# phase1_sheet_97101994.net
KiCad netlist of a schematic drawn in Altium Designer
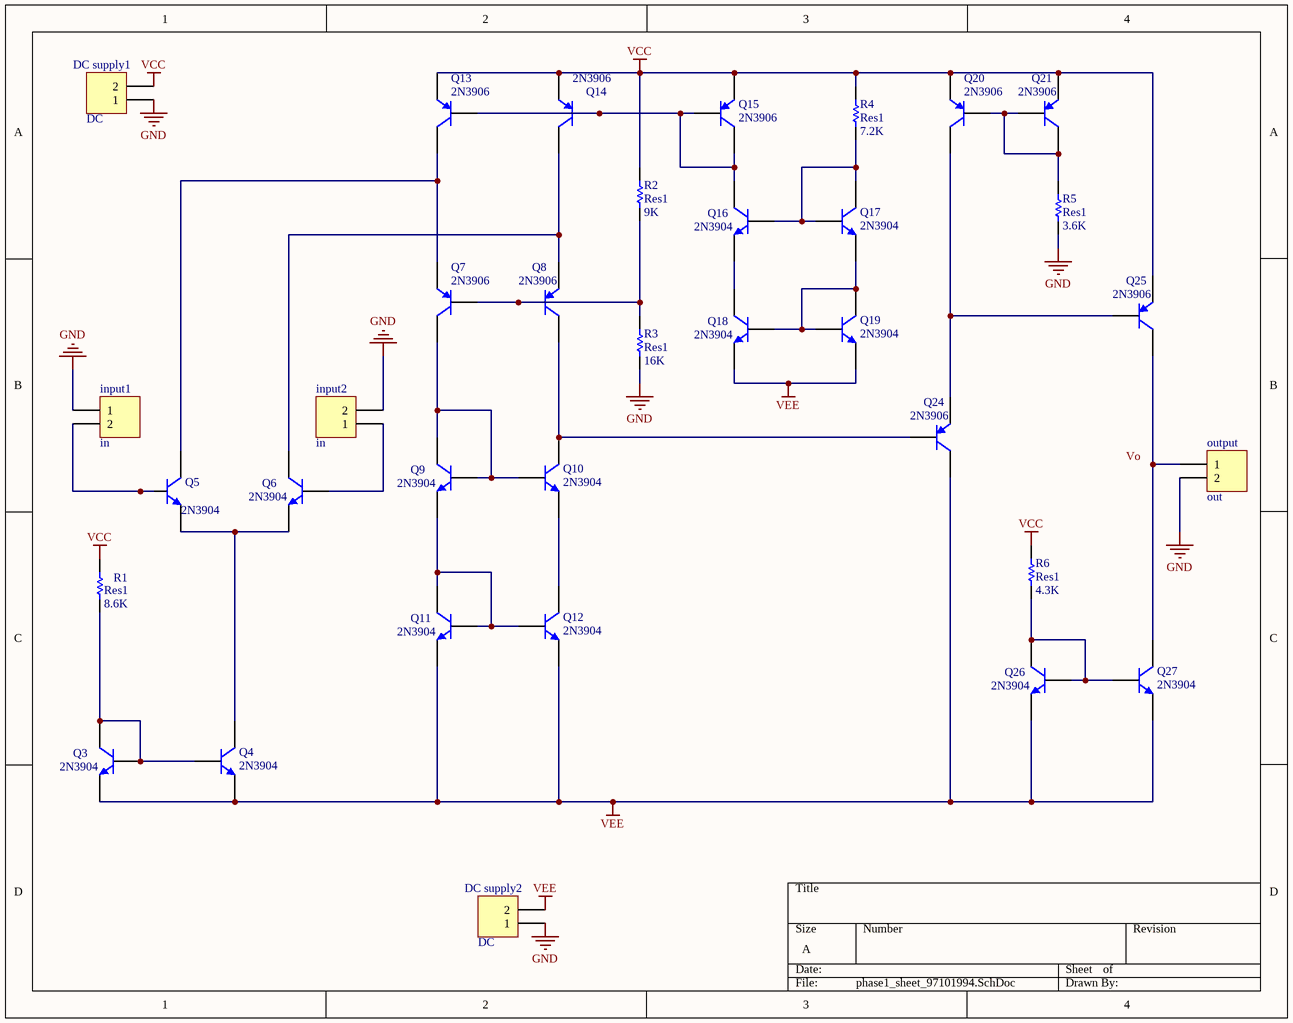
[diagram p0: phase1_sheet_97101994.SchDoc]

(export (version "E")
  (design (tool "Eeschema 10.0.6"))
  (components
    (comp (ref "DC supply1")
      (value "DC")
      (footprint "HDR1X2")
      (description "Header, 2-Pin")
      (fields (field (name "PUBLISHER") "Altium Limited"))
      (libsource (lib "Miscellaneous Connectors") (part "Header 2"))
    )
    (comp (ref "DC supply2")
      (value "DC")
      (footprint "HDR1X2")
      (description "Header, 2-Pin")
      (fields (field (name "PUBLISHER") "Altium Limited"))
      (libsource (lib "Miscellaneous Connectors") (part "Header 2"))
    )
    (comp (ref "input1")
      (value "in")
      (footprint "HDR1X2")
      (description "Header, 2-Pin")
      (fields (field (name "PUBLISHER") "Altium Limited"))
      (libsource (lib "") (part "Header 2_1"))
    )
    (comp (ref "input2")
      (value "in")
      (footprint "HDR1X2")
      (description "Header, 2-Pin")
      (fields (field (name "PUBLISHER") "Altium Limited"))
      (libsource (lib "Miscellaneous Connectors") (part "Header 2"))
    )
    (comp (ref "output")
      (value "out")
      (footprint "HDR1X2")
      (description "Header, 2-Pin")
      (fields (field (name "PUBLISHER") "Altium Limited"))
      (libsource (lib "") (part "Header 2_1"))
    )
    (comp (ref "Q3")
      (value "2N3904")
      (footprint "TO-92A")
      (description "NPN General Purpose Amplifier")
      (fields (field (name "PUBLISHER") "Altium Limited"))
      (libsource (lib "Miscellaneous Devices") (part "2N3904"))
    )
    (comp (ref "Q4")
      (value "2N3904")
      (footprint "TO-92A")
      (description "NPN General Purpose Amplifier")
      (fields (field (name "PUBLISHER") "Altium Limited"))
      (libsource (lib "Miscellaneous Devices") (part "2N3904"))
    )
    (comp (ref "Q5")
      (value "2N3904")
      (footprint "TO-92A")
      (description "NPN General Purpose Amplifier")
      (fields (field (name "PUBLISHER") "Altium Limited"))
      (libsource (lib "Miscellaneous Devices") (part "2N3904"))
    )
    (comp (ref "Q6")
      (value "2N3904")
      (footprint "TO-92A")
      (description "NPN General Purpose Amplifier")
      (fields (field (name "PUBLISHER") "Altium Limited"))
      (libsource (lib "Miscellaneous Devices") (part "2N3904"))
    )
    (comp (ref "Q7")
      (value "2N3906")
      (footprint "TO-92A")
      (description "PNP General Purpose Amplifier")
      (fields (field (name "PUBLISHER") "Altium Limited"))
      (libsource (lib "Miscellaneous Devices") (part "2N3906"))
    )
    (comp (ref "Q8")
      (value "2N3906")
      (footprint "TO-92A")
      (description "PNP General Purpose Amplifier")
      (fields (field (name "PUBLISHER") "Altium Limited"))
      (libsource (lib "Miscellaneous Devices") (part "2N3906"))
    )
    (comp (ref "Q9")
      (value "2N3904")
      (footprint "TO-92A")
      (description "NPN General Purpose Amplifier")
      (fields (field (name "PUBLISHER") "Altium Limited"))
      (libsource (lib "Miscellaneous Devices") (part "2N3904"))
    )
    (comp (ref "Q10")
      (value "2N3904")
      (footprint "TO-92A")
      (description "NPN General Purpose Amplifier")
      (fields (field (name "PUBLISHER") "Altium Limited"))
      (libsource (lib "Miscellaneous Devices") (part "2N3904"))
    )
    (comp (ref "Q11")
      (value "2N3904")
      (footprint "TO-92A")
      (description "NPN General Purpose Amplifier")
      (fields (field (name "PUBLISHER") "Altium Limited"))
      (libsource (lib "Miscellaneous Devices") (part "2N3904"))
    )
    (comp (ref "Q12")
      (value "2N3904")
      (footprint "TO-92A")
      (description "NPN General Purpose Amplifier")
      (fields (field (name "PUBLISHER") "Altium Limited"))
      (libsource (lib "Miscellaneous Devices") (part "2N3904"))
    )
    (comp (ref "Q13")
      (value "2N3906")
      (footprint "TO-92A")
      (description "PNP General Purpose Amplifier")
      (fields (field (name "PUBLISHER") "Altium Limited"))
      (libsource (lib "Miscellaneous Devices") (part "2N3906"))
    )
    (comp (ref "Q14")
      (value "2N3906")
      (footprint "TO-92A")
      (description "PNP General Purpose Amplifier")
      (fields (field (name "PUBLISHER") "Altium Limited"))
      (libsource (lib "Miscellaneous Devices") (part "2N3906"))
    )
    (comp (ref "Q15")
      (value "2N3906")
      (footprint "TO-92A")
      (description "PNP General Purpose Amplifier")
      (fields (field (name "PUBLISHER") "Altium Limited"))
      (libsource (lib "Miscellaneous Devices") (part "2N3906"))
    )
    (comp (ref "Q16")
      (value "2N3904")
      (footprint "TO-92A")
      (description "NPN General Purpose Amplifier")
      (fields (field (name "PUBLISHER") "Altium Limited"))
      (libsource (lib "Miscellaneous Devices") (part "2N3904"))
    )
    (comp (ref "Q17")
      (value "2N3904")
      (footprint "TO-92A")
      (description "NPN General Purpose Amplifier")
      (fields (field (name "PUBLISHER") "Altium Limited"))
      (libsource (lib "Miscellaneous Devices") (part "2N3904"))
    )
    (comp (ref "Q18")
      (value "2N3904")
      (footprint "TO-92A")
      (description "NPN General Purpose Amplifier")
      (fields (field (name "PUBLISHER") "Altium Limited"))
      (libsource (lib "Miscellaneous Devices") (part "2N3904"))
    )
    (comp (ref "Q19")
      (value "2N3904")
      (footprint "TO-92A")
      (description "NPN General Purpose Amplifier")
      (fields (field (name "PUBLISHER") "Altium Limited"))
      (libsource (lib "Miscellaneous Devices") (part "2N3904"))
    )
    (comp (ref "Q20")
      (value "2N3906")
      (footprint "TO-92A")
      (description "PNP General Purpose Amplifier")
      (fields (field (name "PUBLISHER") "Altium Limited"))
      (libsource (lib "Miscellaneous Devices") (part "2N3906"))
    )
    (comp (ref "Q21")
      (value "2N3906")
      (footprint "TO-92A")
      (description "PNP General Purpose Amplifier")
      (fields (field (name "PUBLISHER") "Altium Limited"))
      (libsource (lib "Miscellaneous Devices") (part "2N3906"))
    )
    (comp (ref "Q24")
      (value "2N3906")
      (footprint "TO-92A")
      (description "PNP General Purpose Amplifier")
      (fields (field (name "PUBLISHER") "Altium Limited"))
      (libsource (lib "Miscellaneous Devices") (part "2N3906"))
    )
    (comp (ref "Q25")
      (value "2N3906")
      (footprint "TO-92A")
      (description "PNP General Purpose Amplifier")
      (fields (field (name "PUBLISHER") "Altium Limited"))
      (libsource (lib "Miscellaneous Devices") (part "2N3906"))
    )
    (comp (ref "Q26")
      (value "2N3904")
      (footprint "TO-92A")
      (description "NPN General Purpose Amplifier")
      (fields (field (name "PUBLISHER") "Altium Limited"))
      (libsource (lib "Miscellaneous Devices") (part "2N3904"))
    )
    (comp (ref "Q27")
      (value "2N3904")
      (footprint "TO-92A")
      (description "NPN General Purpose Amplifier")
      (fields (field (name "PUBLISHER") "Altium Limited"))
      (libsource (lib "Miscellaneous Devices") (part "2N3904"))
    )
    (comp (ref "R1")
      (value "Res1")
      (footprint "AXIAL-0.3")
      (description "Resistor")
      (fields (field (name "ALTIUM_VALUE") "8.6K") (field (name "PUBLISHER") "Altium Limited"))
      (libsource (lib "Miscellaneous Devices") (part "Res1"))
    )
    (comp (ref "R2")
      (value "Res1")
      (footprint "AXIAL-0.3")
      (description "Resistor")
      (fields (field (name "ALTIUM_VALUE") "9K") (field (name "PUBLISHER") "Altium Limited"))
      (libsource (lib "Miscellaneous Devices") (part "Res1"))
    )
    (comp (ref "R3")
      (value "Res1")
      (footprint "AXIAL-0.3")
      (description "Resistor")
      (fields (field (name "ALTIUM_VALUE") "16K") (field (name "PUBLISHER") "Altium Limited"))
      (libsource (lib "Miscellaneous Devices") (part "Res1"))
    )
    (comp (ref "R4")
      (value "Res1")
      (footprint "AXIAL-0.3")
      (description "Resistor")
      (fields (field (name "ALTIUM_VALUE") "7.2K") (field (name "PUBLISHER") "Altium Limited"))
      (libsource (lib "Miscellaneous Devices") (part "Res1"))
    )
    (comp (ref "R5")
      (value "Res1")
      (footprint "AXIAL-0.3")
      (description "Resistor")
      (fields (field (name "ALTIUM_VALUE") "3.6K") (field (name "PUBLISHER") "Altium Limited"))
      (libsource (lib "Miscellaneous Devices") (part "Res1"))
    )
    (comp (ref "R6")
      (value "Res1")
      (footprint "AXIAL-0.3")
      (description "Resistor")
      (fields (field (name "ALTIUM_VALUE") "4.3K") (field (name "PUBLISHER") "Altium Limited"))
      (libsource (lib "Miscellaneous Devices") (part "Res1"))
    )
  )
  (nets
    (net (code "2") (name "GND") (class "Default")
      (node (ref "DC supply1") (pin "1") (pinfunction "1_1") (pintype "passive"))
      (node (ref "DC supply2") (pin "1") (pinfunction "1_1") (pintype "passive"))
      (node (ref "R3") (pin "1") (pinfunction "1_1") (pintype "passive"))
      (node (ref "R5") (pin "1") (pinfunction "1_1") (pintype "passive"))
      (node (ref "input1") (pin "1") (pinfunction "1_1") (pintype "passive"))
      (node (ref "input2") (pin "2") (pinfunction "2_2") (pintype "passive"))
      (node (ref "output") (pin "2") (pinfunction "2_2") (pintype "passive"))
    )
    (net (code "3") (name "Net-(Q3-B)") (class "Default")
      (node (ref "Q3") (pin "2") (pinfunction "B_2") (pintype "passive"))
      (node (ref "Q3") (pin "3") (pinfunction "C_3") (pintype "passive"))
      (node (ref "Q4") (pin "2") (pinfunction "B_2") (pintype "passive"))
      (node (ref "R1") (pin "1") (pinfunction "1_1") (pintype "passive"))
    )
    (net (code "4") (name "Net-(Q4-C)") (class "Default")
      (node (ref "Q4") (pin "3") (pinfunction "C_3") (pintype "passive"))
      (node (ref "Q5") (pin "1") (pinfunction "E_1") (pintype "passive"))
      (node (ref "Q6") (pin "1") (pinfunction "E_1") (pintype "passive"))
    )
    (net (code "5") (name "Net-(Q5-B)") (class "Default")
      (node (ref "Q5") (pin "2") (pinfunction "B_2") (pintype "passive"))
      (node (ref "input1") (pin "2") (pinfunction "2_2") (pintype "passive"))
    )
    (net (code "6") (name "Net-(Q6-B)") (class "Default")
      (node (ref "Q6") (pin "2") (pinfunction "B_2") (pintype "passive"))
      (node (ref "input2") (pin "1") (pinfunction "1_1") (pintype "passive"))
    )
    (net (code "7") (name "Net-(Q7-B)") (class "Default")
      (node (ref "Q7") (pin "2") (pinfunction "B_2") (pintype "passive"))
      (node (ref "Q8") (pin "2") (pinfunction "B_2") (pintype "passive"))
      (node (ref "R2") (pin "1") (pinfunction "1_1") (pintype "passive"))
      (node (ref "R3") (pin "2") (pinfunction "2_2") (pintype "passive"))
    )
    (net (code "8") (name "Net-(Q10-B)") (class "Default")
      (node (ref "Q10") (pin "2") (pinfunction "B_2") (pintype "passive"))
      (node (ref "Q7") (pin "3") (pinfunction "C_3") (pintype "passive"))
      (node (ref "Q9") (pin "2") (pinfunction "B_2") (pintype "passive"))
      (node (ref "Q9") (pin "3") (pinfunction "C_3") (pintype "passive"))
    )
    (net (code "9") (name "Net-(Q10-C)") (class "Default")
      (node (ref "Q10") (pin "3") (pinfunction "C_3") (pintype "passive"))
      (node (ref "Q24") (pin "2") (pinfunction "B_2") (pintype "passive"))
      (node (ref "Q8") (pin "3") (pinfunction "C_3") (pintype "passive"))
    )
    (net (code "10") (name "Net-(Q10-E)") (class "Default")
      (node (ref "Q10") (pin "1") (pinfunction "E_1") (pintype "passive"))
      (node (ref "Q12") (pin "3") (pinfunction "C_3") (pintype "passive"))
    )
    (net (code "11") (name "Net-(Q11-B)") (class "Default")
      (node (ref "Q11") (pin "2") (pinfunction "B_2") (pintype "passive"))
      (node (ref "Q11") (pin "3") (pinfunction "C_3") (pintype "passive"))
      (node (ref "Q12") (pin "2") (pinfunction "B_2") (pintype "passive"))
      (node (ref "Q9") (pin "1") (pinfunction "E_1") (pintype "passive"))
    )
    (net (code "12") (name "Net-(Q13-B)") (class "Default")
      (node (ref "Q13") (pin "2") (pinfunction "B_2") (pintype "passive"))
      (node (ref "Q14") (pin "2") (pinfunction "B_2") (pintype "passive"))
      (node (ref "Q15") (pin "2") (pinfunction "B_2") (pintype "passive"))
      (node (ref "Q15") (pin "3") (pinfunction "C_3") (pintype "passive"))
      (node (ref "Q16") (pin "3") (pinfunction "C_3") (pintype "passive"))
    )
    (net (code "13") (name "Net-(Q13-C)") (class "Default")
      (node (ref "Q13") (pin "3") (pinfunction "C_3") (pintype "passive"))
      (node (ref "Q5") (pin "3") (pinfunction "C_3") (pintype "passive"))
      (node (ref "Q7") (pin "1") (pinfunction "E_1") (pintype "passive"))
    )
    (net (code "14") (name "Net-(Q14-C)") (class "Default")
      (node (ref "Q14") (pin "3") (pinfunction "C_3") (pintype "passive"))
      (node (ref "Q6") (pin "3") (pinfunction "C_3") (pintype "passive"))
      (node (ref "Q8") (pin "1") (pinfunction "E_1") (pintype "passive"))
    )
    (net (code "15") (name "Net-(Q16-B)") (class "Default")
      (node (ref "Q16") (pin "2") (pinfunction "B_2") (pintype "passive"))
      (node (ref "Q17") (pin "2") (pinfunction "B_2") (pintype "passive"))
      (node (ref "Q17") (pin "3") (pinfunction "C_3") (pintype "passive"))
      (node (ref "R4") (pin "1") (pinfunction "1_1") (pintype "passive"))
    )
    (net (code "16") (name "Net-(Q16-E)") (class "Default")
      (node (ref "Q16") (pin "1") (pinfunction "E_1") (pintype "passive"))
      (node (ref "Q18") (pin "3") (pinfunction "C_3") (pintype "passive"))
    )
    (net (code "17") (name "Net-(Q17-E)") (class "Default")
      (node (ref "Q17") (pin "1") (pinfunction "E_1") (pintype "passive"))
      (node (ref "Q18") (pin "2") (pinfunction "B_2") (pintype "passive"))
      (node (ref "Q19") (pin "2") (pinfunction "B_2") (pintype "passive"))
      (node (ref "Q19") (pin "3") (pinfunction "C_3") (pintype "passive"))
    )
    (net (code "18") (name "Net-(Q20-B)") (class "Default")
      (node (ref "Q20") (pin "2") (pinfunction "B_2") (pintype "passive"))
      (node (ref "Q21") (pin "2") (pinfunction "B_2") (pintype "passive"))
      (node (ref "Q21") (pin "3") (pinfunction "C_3") (pintype "passive"))
      (node (ref "R5") (pin "2") (pinfunction "2_2") (pintype "passive"))
    )
    (net (code "19") (name "Net-(Q20-C)") (class "Default")
      (node (ref "Q20") (pin "3") (pinfunction "C_3") (pintype "passive"))
      (node (ref "Q24") (pin "1") (pinfunction "E_1") (pintype "passive"))
      (node (ref "Q25") (pin "2") (pinfunction "B_2") (pintype "passive"))
    )
    (net (code "20") (name "Net-(Q25-C)") (class "Default")
      (node (ref "Q25") (pin "3") (pinfunction "C_3") (pintype "passive"))
      (node (ref "Q27") (pin "3") (pinfunction "C_3") (pintype "passive"))
      (node (ref "output") (pin "1") (pinfunction "1_1") (pintype "passive"))
    )
    (net (code "21") (name "Net-(Q26-B)") (class "Default")
      (node (ref "Q26") (pin "2") (pinfunction "B_2") (pintype "passive"))
      (node (ref "Q26") (pin "3") (pinfunction "C_3") (pintype "passive"))
      (node (ref "Q27") (pin "2") (pinfunction "B_2") (pintype "passive"))
      (node (ref "R6") (pin "1") (pinfunction "1_1") (pintype "passive"))
    )
    (net (code "22") (name "VCC") (class "Default")
      (node (ref "DC supply1") (pin "2") (pinfunction "2_2") (pintype "passive"))
      (node (ref "Q13") (pin "1") (pinfunction "E_1") (pintype "passive"))
      (node (ref "Q14") (pin "1") (pinfunction "E_1") (pintype "passive"))
      (node (ref "Q15") (pin "1") (pinfunction "E_1") (pintype "passive"))
      (node (ref "Q20") (pin "1") (pinfunction "E_1") (pintype "passive"))
      (node (ref "Q21") (pin "1") (pinfunction "E_1") (pintype "passive"))
      (node (ref "Q25") (pin "1") (pinfunction "E_1") (pintype "passive"))
      (node (ref "R1") (pin "2") (pinfunction "2_2") (pintype "passive"))
      (node (ref "R2") (pin "2") (pinfunction "2_2") (pintype "passive"))
      (node (ref "R4") (pin "2") (pinfunction "2_2") (pintype "passive"))
      (node (ref "R6") (pin "2") (pinfunction "2_2") (pintype "passive"))
    )
    (net (code "23") (name "VEE") (class "Default")
      (node (ref "DC supply2") (pin "2") (pinfunction "2_2") (pintype "passive"))
      (node (ref "Q11") (pin "1") (pinfunction "E_1") (pintype "passive"))
      (node (ref "Q12") (pin "1") (pinfunction "E_1") (pintype "passive"))
      (node (ref "Q18") (pin "1") (pinfunction "E_1") (pintype "passive"))
      (node (ref "Q19") (pin "1") (pinfunction "E_1") (pintype "passive"))
      (node (ref "Q24") (pin "3") (pinfunction "C_3") (pintype "passive"))
      (node (ref "Q26") (pin "1") (pinfunction "E_1") (pintype "passive"))
      (node (ref "Q27") (pin "1") (pinfunction "E_1") (pintype "passive"))
      (node (ref "Q3") (pin "1") (pinfunction "E_1") (pintype "passive"))
      (node (ref "Q4") (pin "1") (pinfunction "E_1") (pintype "passive"))
    )
  )
)
